# FTDI-Breakout_v21.net
KiCad netlist of a schematic drawn in EAGLE
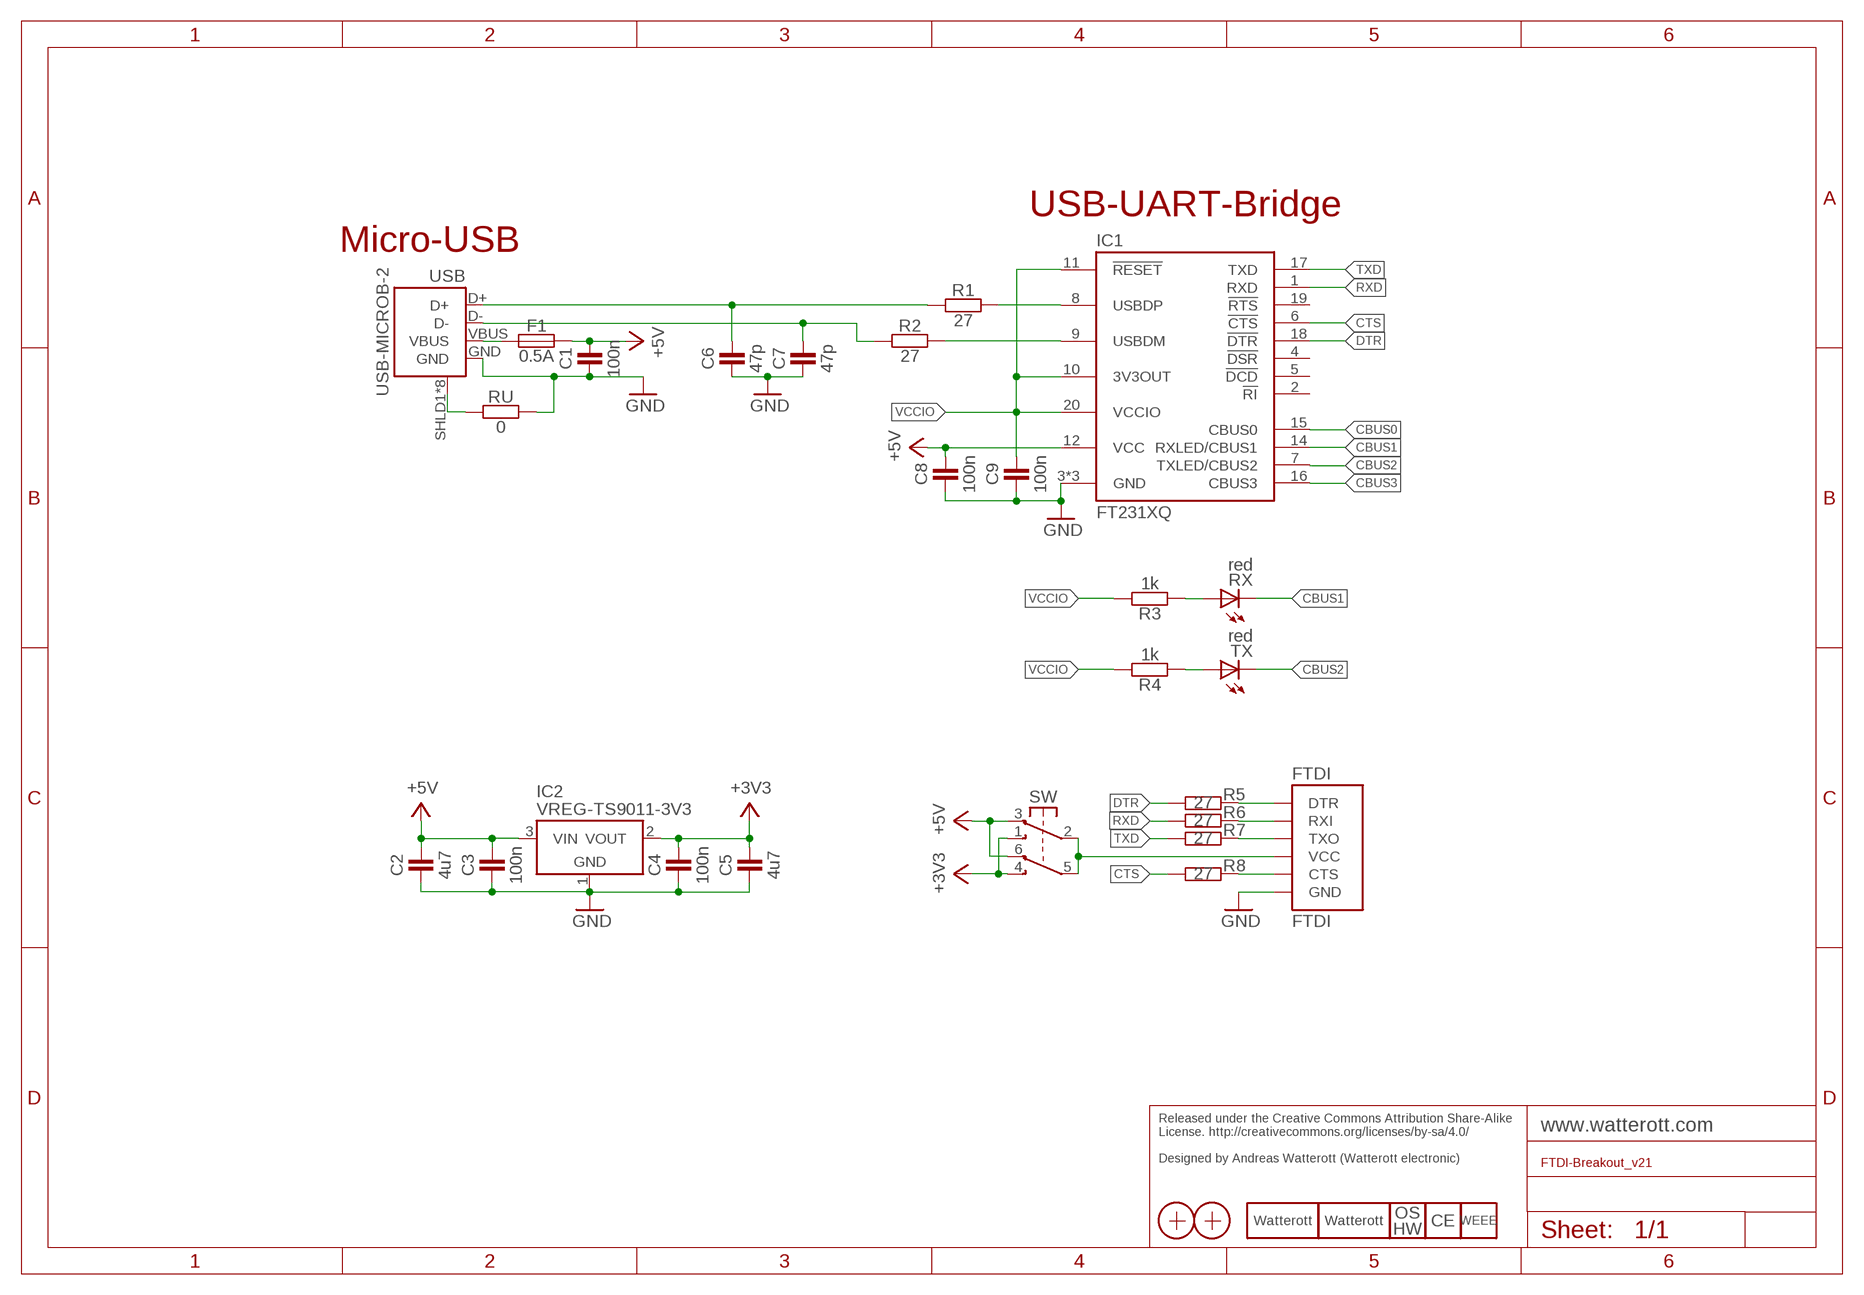
[diagram p0: schematic, sheet 1]

(export (version "E")
  (design (tool "Eeschema 10.0.6"))
  (components
    (comp (ref "C1")
      (value "100n")
      (footprint "eagle-import:C0603")
      (libsource (lib "eagle-import") (part "CAPACITOR-0603"))
    )
    (comp (ref "C2")
      (value "4u7")
      (footprint "eagle-import:C0805")
      (libsource (lib "eagle-import") (part "CAPACITOR-0805"))
    )
    (comp (ref "C3")
      (value "100n")
      (footprint "eagle-import:C0603")
      (libsource (lib "eagle-import") (part "CAPACITOR-0603"))
    )
    (comp (ref "C4")
      (value "100n")
      (footprint "eagle-import:C0603")
      (libsource (lib "eagle-import") (part "CAPACITOR-0603"))
    )
    (comp (ref "C5")
      (value "4u7")
      (footprint "eagle-import:C0805")
      (libsource (lib "eagle-import") (part "CAPACITOR-0805"))
    )
    (comp (ref "C6")
      (value "47p")
      (footprint "eagle-import:C0603")
      (libsource (lib "eagle-import") (part "CAPACITOR-0603"))
    )
    (comp (ref "C7")
      (value "47p")
      (footprint "eagle-import:C0603")
      (libsource (lib "eagle-import") (part "CAPACITOR-0603"))
    )
    (comp (ref "C8")
      (value "100n")
      (footprint "eagle-import:C0603")
      (libsource (lib "eagle-import") (part "CAPACITOR-0603"))
    )
    (comp (ref "C9")
      (value "100n")
      (footprint "eagle-import:C0603")
      (libsource (lib "eagle-import") (part "CAPACITOR-0603"))
    )
    (comp (ref "F1")
      (value "0.5A")
      (footprint "eagle-import:C0805")
      (libsource (lib "eagle-import") (part "FUSE-0805"))
    )
    (comp (ref "FTDI")
      (value "FTDI")
      (footprint "eagle-import:FTDI")
      (libsource (lib "eagle-import") (part "FTDI"))
    )
    (comp (ref "IC1")
      (value "FT231XQ")
      (footprint "eagle-import:QFN20-PAD")
      (libsource (lib "eagle-import") (part "FT231XQ"))
    )
    (comp (ref "IC2")
      (value "VREG-TS9011-3V3")
      (footprint "eagle-import:SOT23")
      (libsource (lib "eagle-import") (part "VREG-TS9011-3V3"))
    )
    (comp (ref "LOGO5")
      (value "LOGO_SPARK-2")
      (footprint "eagle-import:SPARK_2MM")
      (libsource (lib "eagle-import") (part "LOGO_SPARK-2"))
    )
    (comp (ref "LOGO6")
      (value "LOGO_SPARK-4")
      (footprint "eagle-import:SPARK_4MM")
      (libsource (lib "eagle-import") (part "LOGO_SPARK-4"))
    )
    (comp (ref "LOGO7")
      (value "LOGO_OSHW-2")
      (footprint "eagle-import:OSHW_2MM")
      (libsource (lib "eagle-import") (part "LOGO_OSHW-2"))
    )
    (comp (ref "LOGO8")
      (value "LOGO_CE-2")
      (footprint "eagle-import:CE_2MM")
      (libsource (lib "eagle-import") (part "LOGO_CE-2"))
    )
    (comp (ref "LOGO9")
      (value "LOGO_WEEE-4")
      (footprint "eagle-import:WEEE_4MM")
      (libsource (lib "eagle-import") (part "LOGO_WEEE-4"))
    )
    (comp (ref "R1")
      (value "27")
      (footprint "eagle-import:C0603")
      (libsource (lib "eagle-import") (part "RESISTOR-0603"))
    )
    (comp (ref "R2")
      (value "27")
      (footprint "eagle-import:C0603")
      (libsource (lib "eagle-import") (part "RESISTOR-0603"))
    )
    (comp (ref "R3")
      (value "1k")
      (footprint "eagle-import:C0603")
      (libsource (lib "eagle-import") (part "RESISTOR-0603"))
    )
    (comp (ref "R4")
      (value "1k")
      (footprint "eagle-import:C0603")
      (libsource (lib "eagle-import") (part "RESISTOR-0603"))
    )
    (comp (ref "R5")
      (value "27")
      (footprint "eagle-import:C0603")
      (libsource (lib "eagle-import") (part "RESISTOR-0603"))
    )
    (comp (ref "R6")
      (value "27")
      (footprint "eagle-import:C0603")
      (libsource (lib "eagle-import") (part "RESISTOR-0603"))
    )
    (comp (ref "R7")
      (value "27")
      (footprint "eagle-import:C0603")
      (libsource (lib "eagle-import") (part "RESISTOR-0603"))
    )
    (comp (ref "R8")
      (value "27")
      (footprint "eagle-import:C0603")
      (libsource (lib "eagle-import") (part "RESISTOR-0603"))
    )
    (comp (ref "RU")
      (value "0")
      (footprint "eagle-import:C0603")
      (libsource (lib "eagle-import") (part "RESISTOR-0603"))
    )
    (comp (ref "RX")
      (value "red")
      (footprint "eagle-import:C0603")
      (libsource (lib "eagle-import") (part "LED-0603"))
    )
    (comp (ref "SW")
      (value "SW-2UM-CUS22B")
      (footprint "eagle-import:CUS22B")
      (libsource (lib "eagle-import") (part "SW-2UM-CUS22B"))
    )
    (comp (ref "TX")
      (value "red")
      (footprint "eagle-import:C0603")
      (libsource (lib "eagle-import") (part "LED-0603"))
    )
    (comp (ref "USB")
      (value "USB-MICROB-2")
      (footprint "eagle-import:USB-MICROB-10118194")
      (libsource (lib "eagle-import") (part "USB-MICROB-2"))
    )
    (comp (ref "X1")
      (value "PASSER-07")
      (footprint "eagle-import:PASSER_07MM")
      (libsource (lib "eagle-import") (part "PASSER-07"))
    )
    (comp (ref "X2")
      (value "PASSER-07")
      (footprint "eagle-import:PASSER_07MM")
      (libsource (lib "eagle-import") (part "PASSER-07"))
    )
  )
  (nets
    (net (code "1") (name "+3V3") (class "Default")
      (node (ref "C4") (pin "2") (pinfunction "2_2") (pintype "passive"))
      (node (ref "C5") (pin "2") (pinfunction "2_2") (pintype "passive"))
      (node (ref "IC2") (pin "2") (pinfunction "VOUT_2") (pintype "power_in"))
      (node (ref "SW") (pin "1") (pinfunction "S1_1") (pintype "passive"))
      (node (ref "SW") (pin "4") (pinfunction "S2_4") (pintype "passive"))
    )
    (net (code "2") (name "+5V") (class "Default")
      (node (ref "C1") (pin "2") (pinfunction "2_2") (pintype "passive"))
      (node (ref "C2") (pin "2") (pinfunction "2_2") (pintype "passive"))
      (node (ref "C3") (pin "2") (pinfunction "2_2") (pintype "passive"))
      (node (ref "C8") (pin "2") (pinfunction "2_2") (pintype "passive"))
      (node (ref "F1") (pin "2") (pinfunction "2_2") (pintype "passive"))
      (node (ref "IC1") (pin "12") (pinfunction "VCC_12") (pintype "power_in"))
      (node (ref "IC2") (pin "3") (pinfunction "VIN_3") (pintype "power_in"))
      (node (ref "SW") (pin "3") (pinfunction "O1_3") (pintype "passive"))
      (node (ref "SW") (pin "6") (pinfunction "O2_6") (pintype "passive"))
    )
    (net (code "3") (name "CBUS0") (class "Default")
      (node (ref "IC1") (pin "15") (pinfunction "CBUS0_15") (pintype "bidirectional"))
    )
    (net (code "4") (name "CBUS1") (class "Default")
      (node (ref "IC1") (pin "14") (pinfunction "RXLED/CBUS1_14") (pintype "bidirectional"))
      (node (ref "RX") (pin "C") (pinfunction "C_C") (pintype "passive"))
    )
    (net (code "5") (name "CBUS2") (class "Default")
      (node (ref "IC1") (pin "7") (pinfunction "TXLED/CBUS2_7") (pintype "bidirectional"))
      (node (ref "TX") (pin "C") (pinfunction "C_C") (pintype "passive"))
    )
    (net (code "6") (name "CBUS3") (class "Default")
      (node (ref "IC1") (pin "16") (pinfunction "CBUS3_16") (pintype "bidirectional"))
    )
    (net (code "7") (name "CTS") (class "Default")
      (node (ref "IC1") (pin "6") (pinfunction "~{CTS}_6") (pintype "bidirectional"))
      (node (ref "R8") (pin "1") (pinfunction "1_1") (pintype "passive"))
    )
    (net (code "8") (name "DTR") (class "Default")
      (node (ref "IC1") (pin "18") (pinfunction "~{DTR}_18") (pintype "bidirectional"))
      (node (ref "R5") (pin "1") (pinfunction "1_1") (pintype "passive"))
    )
    (net (code "9") (name "GND") (class "Default")
      (node (ref "C1") (pin "1") (pinfunction "1_1") (pintype "passive"))
      (node (ref "C2") (pin "1") (pinfunction "1_1") (pintype "passive"))
      (node (ref "C3") (pin "1") (pinfunction "1_1") (pintype "passive"))
      (node (ref "C4") (pin "1") (pinfunction "1_1") (pintype "passive"))
      (node (ref "C5") (pin "1") (pinfunction "1_1") (pintype "passive"))
      (node (ref "C6") (pin "1") (pinfunction "1_1") (pintype "passive"))
      (node (ref "C7") (pin "1") (pinfunction "1_1") (pintype "passive"))
      (node (ref "C8") (pin "1") (pinfunction "1_1") (pintype "passive"))
      (node (ref "C9") (pin "1") (pinfunction "1_1") (pintype "passive"))
      (node (ref "FTDI") (pin "1-GND") (pinfunction "GND_1-GND") (pintype "power_in"))
      (node (ref "IC1") (pin "13") (pinfunction "GND_13") (pintype "power_in"))
      (node (ref "IC1") (pin "3") (pinfunction "GND_3") (pintype "power_in"))
      (node (ref "IC1") (pin "TP") (pinfunction "GND_TP") (pintype "power_in"))
      (node (ref "IC2") (pin "1") (pinfunction "GND_1") (pintype "power_in"))
      (node (ref "RU") (pin "2") (pinfunction "2_2") (pintype "passive"))
      (node (ref "USB") (pin "GND") (pinfunction "GND_GND") (pintype "power_in"))
    )
    (net (code "10") (name "Net-(C6-Pad2)") (class "Default")
      (node (ref "C6") (pin "2") (pinfunction "2_2") (pintype "passive"))
      (node (ref "R1") (pin "1") (pinfunction "1_1") (pintype "passive"))
      (node (ref "USB") (pin "D+") (pinfunction "D+_D+") (pintype "bidirectional"))
    )
    (net (code "11") (name "Net-(C7-Pad2)") (class "Default")
      (node (ref "C7") (pin "2") (pinfunction "2_2") (pintype "passive"))
      (node (ref "R2") (pin "1") (pinfunction "1_1") (pintype "passive"))
      (node (ref "USB") (pin "D-") (pinfunction "D-_D-") (pintype "bidirectional"))
    )
    (net (code "12") (name "Net-(F1-Pad1)") (class "Default")
      (node (ref "F1") (pin "1") (pinfunction "1_1") (pintype "passive"))
      (node (ref "USB") (pin "VBUS") (pinfunction "VBUS_VBUS") (pintype "power_in"))
    )
    (net (code "13") (name "Net-(FTDI-CTS)") (class "Default")
      (node (ref "FTDI") (pin "2-CTS") (pinfunction "CTS_2-CTS") (pintype "bidirectional"))
      (node (ref "R8") (pin "2") (pinfunction "2_2") (pintype "passive"))
    )
    (net (code "14") (name "Net-(FTDI-DTR)") (class "Default")
      (node (ref "FTDI") (pin "6-DTR") (pinfunction "DTR_6-DTR") (pintype "bidirectional"))
      (node (ref "R5") (pin "2") (pinfunction "2_2") (pintype "passive"))
    )
    (net (code "15") (name "Net-(FTDI-RXI)") (class "Default")
      (node (ref "FTDI") (pin "5-RXI") (pinfunction "RXI_5-RXI") (pintype "bidirectional"))
      (node (ref "R6") (pin "2") (pinfunction "2_2") (pintype "passive"))
    )
    (net (code "16") (name "Net-(FTDI-TXO)") (class "Default")
      (node (ref "FTDI") (pin "4-TXO") (pinfunction "TXO_4-TXO") (pintype "bidirectional"))
      (node (ref "R7") (pin "2") (pinfunction "2_2") (pintype "passive"))
    )
    (net (code "17") (name "Net-(FTDI-VCC)") (class "Default")
      (node (ref "FTDI") (pin "3-VCC") (pinfunction "VCC_3-VCC") (pintype "power_in"))
      (node (ref "SW") (pin "2") (pinfunction "P1_2") (pintype "passive"))
      (node (ref "SW") (pin "5") (pinfunction "P2_5") (pintype "passive"))
    )
    (net (code "18") (name "Net-(IC1-USBDM)") (class "Default")
      (node (ref "IC1") (pin "9") (pinfunction "USBDM_9") (pintype "bidirectional"))
      (node (ref "R2") (pin "2") (pinfunction "2_2") (pintype "passive"))
    )
    (net (code "19") (name "Net-(IC1-USBDP)") (class "Default")
      (node (ref "IC1") (pin "8") (pinfunction "USBDP_8") (pintype "bidirectional"))
      (node (ref "R1") (pin "2") (pinfunction "2_2") (pintype "passive"))
    )
    (net (code "20") (name "Net-(R3-Pad1)") (class "Default")
      (node (ref "R3") (pin "1") (pinfunction "1_1") (pintype "passive"))
      (node (ref "RX") (pin "A") (pinfunction "A_A") (pintype "passive"))
    )
    (net (code "21") (name "Net-(R4-Pad1)") (class "Default")
      (node (ref "R4") (pin "1") (pinfunction "1_1") (pintype "passive"))
      (node (ref "TX") (pin "A") (pinfunction "A_A") (pintype "passive"))
    )
    (net (code "22") (name "Net-(RU-Pad1)") (class "Default")
      (node (ref "RU") (pin "1") (pinfunction "1_1") (pintype "passive"))
      (node (ref "USB") (pin "SHLD1") (pinfunction "SHIELD_SHLD1") (pintype "passive"))
      (node (ref "USB") (pin "SHLD2") (pinfunction "SHIELD_SHLD2") (pintype "passive"))
      (node (ref "USB") (pin "SHLD3") (pinfunction "SHIELD_SHLD3") (pintype "passive"))
      (node (ref "USB") (pin "SHLD4") (pinfunction "SHIELD_SHLD4") (pintype "passive"))
      (node (ref "USB") (pin "SHLD5") (pinfunction "SHIELD_SHLD5") (pintype "passive"))
      (node (ref "USB") (pin "SHLD6") (pinfunction "SHIELD_SHLD6") (pintype "passive"))
      (node (ref "USB") (pin "SHLD7") (pinfunction "SHIELD_SHLD7") (pintype "passive"))
      (node (ref "USB") (pin "SHLD8") (pinfunction "SHIELD_SHLD8") (pintype "passive"))
    )
    (net (code "23") (name "RXD") (class "Default")
      (node (ref "IC1") (pin "1") (pinfunction "RXD_1") (pintype "bidirectional"))
      (node (ref "R6") (pin "1") (pinfunction "1_1") (pintype "passive"))
    )
    (net (code "24") (name "TXD") (class "Default")
      (node (ref "IC1") (pin "17") (pinfunction "TXD_17") (pintype "bidirectional"))
      (node (ref "R7") (pin "1") (pinfunction "1_1") (pintype "passive"))
    )
    (net (code "25") (name "VCCIO") (class "Default")
      (node (ref "C9") (pin "2") (pinfunction "2_2") (pintype "passive"))
      (node (ref "IC1") (pin "10") (pinfunction "3V3OUT_10") (pintype "power_in"))
      (node (ref "IC1") (pin "11") (pinfunction "~{RESET}_11") (pintype "bidirectional"))
      (node (ref "IC1") (pin "20") (pinfunction "VCCIO_20") (pintype "power_in"))
      (node (ref "R3") (pin "2") (pinfunction "2_2") (pintype "passive"))
      (node (ref "R4") (pin "2") (pinfunction "2_2") (pintype "passive"))
    )
    (net (code "26") (name "unconnected-(IC1-~{DCD}-Pad5)") (class "Default")
      (node (ref "IC1") (pin "5") (pinfunction "~{DCD}_5") (pintype "bidirectional"))
    )
    (net (code "27") (name "unconnected-(IC1-~{DSR}-Pad4)") (class "Default")
      (node (ref "IC1") (pin "4") (pinfunction "~{DSR}_4") (pintype "bidirectional"))
    )
    (net (code "28") (name "unconnected-(IC1-~{RI}-Pad2)") (class "Default")
      (node (ref "IC1") (pin "2") (pinfunction "~{RI}_2") (pintype "bidirectional"))
    )
    (net (code "29") (name "unconnected-(IC1-~{RTS}-Pad19)") (class "Default")
      (node (ref "IC1") (pin "19") (pinfunction "~{RTS}_19") (pintype "bidirectional"))
    )
  )
)
